# robocon_line_following_sensor_compact.net
KiCad netlist of a schematic drawn in EAGLE
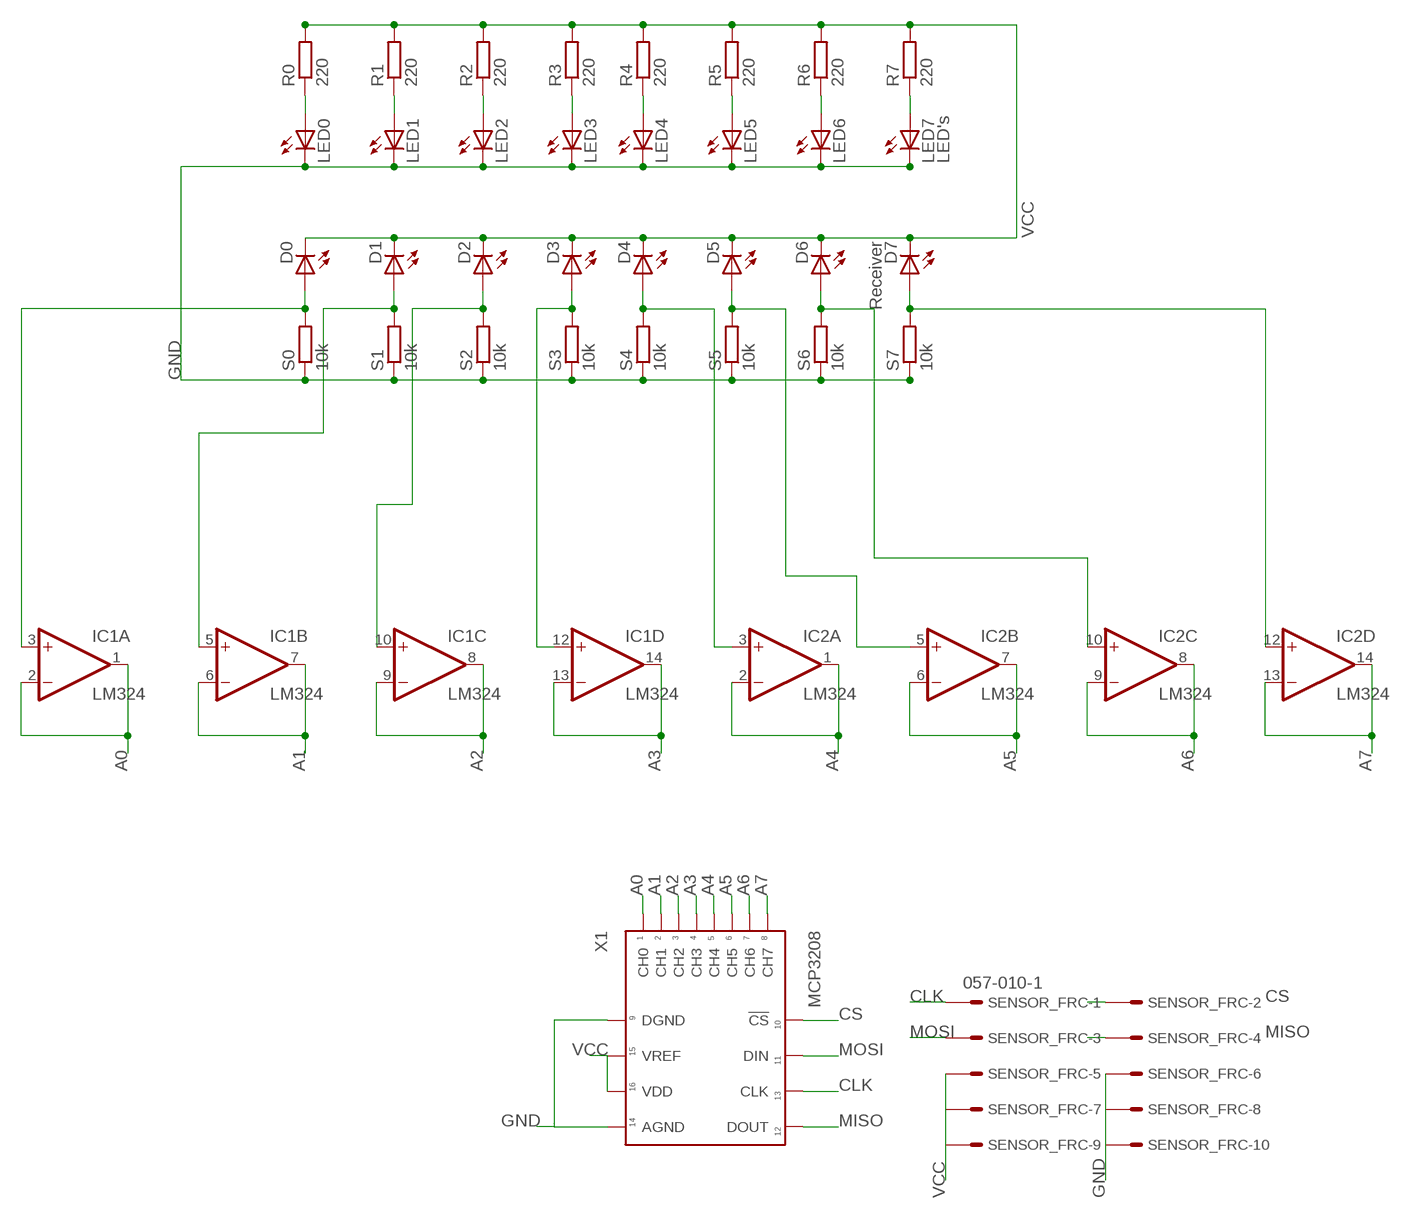
[diagram p0: schematic, sheet 1]

(export (version "E")
  (design (tool "Eeschema 10.0.6"))
  (components
    (comp (ref "D0")
      (value "LED5MM")
      (footprint "eagle-import:LED5MM")
      (libsource (lib "eagle-import") (part "LED5MM"))
    )
    (comp (ref "D1")
      (value "LED5MM")
      (footprint "eagle-import:LED5MM")
      (libsource (lib "eagle-import") (part "LED5MM"))
    )
    (comp (ref "D2")
      (value "LED5MM")
      (footprint "eagle-import:LED5MM")
      (libsource (lib "eagle-import") (part "LED5MM"))
    )
    (comp (ref "D3")
      (value "LED5MM")
      (footprint "eagle-import:LED5MM")
      (libsource (lib "eagle-import") (part "LED5MM"))
    )
    (comp (ref "D4")
      (value "LED5MM")
      (footprint "eagle-import:LED5MM")
      (libsource (lib "eagle-import") (part "LED5MM"))
    )
    (comp (ref "D5")
      (value "LED5MM")
      (footprint "eagle-import:LED5MM")
      (libsource (lib "eagle-import") (part "LED5MM"))
    )
    (comp (ref "D6")
      (value "LED5MM")
      (footprint "eagle-import:LED5MM")
      (libsource (lib "eagle-import") (part "LED5MM"))
    )
    (comp (ref "D7")
      (value "Receiver")
      (footprint "eagle-import:LED5MM")
      (libsource (lib "eagle-import") (part "LED5MM"))
    )
    (comp (ref "IC1")
      (value "LM324")
      (footprint "eagle-import:DIL14")
      (libsource (lib "eagle-import") (part "LM324N"))
    )
    (comp (ref "IC2")
      (value "LM324")
      (footprint "eagle-import:DIL14")
      (libsource (lib "eagle-import") (part "LM324N"))
    )
    (comp (ref "LED0")
      (value "LED5MM")
      (footprint "eagle-import:LED5MM")
      (libsource (lib "eagle-import") (part "LED5MM"))
    )
    (comp (ref "LED1")
      (value "LED5MM")
      (footprint "eagle-import:LED5MM")
      (libsource (lib "eagle-import") (part "LED5MM"))
    )
    (comp (ref "LED2")
      (value "LED5MM")
      (footprint "eagle-import:LED5MM")
      (libsource (lib "eagle-import") (part "LED5MM"))
    )
    (comp (ref "LED3")
      (value "LED5MM")
      (footprint "eagle-import:LED5MM")
      (libsource (lib "eagle-import") (part "LED5MM"))
    )
    (comp (ref "LED4")
      (value "LED5MM")
      (footprint "eagle-import:LED5MM")
      (libsource (lib "eagle-import") (part "LED5MM"))
    )
    (comp (ref "LED5")
      (value "LED5MM")
      (footprint "eagle-import:LED5MM")
      (libsource (lib "eagle-import") (part "LED5MM"))
    )
    (comp (ref "LED6")
      (value "LED5MM")
      (footprint "eagle-import:LED5MM")
      (libsource (lib "eagle-import") (part "LED5MM"))
    )
    (comp (ref "LED7")
      (value "LED's")
      (footprint "eagle-import:LED5MM")
      (libsource (lib "eagle-import") (part "LED5MM"))
    )
    (comp (ref "R0")
      (value "220")
      (footprint "eagle-import:0207_10")
      (libsource (lib "eagle-import") (part "R-EU_0207/10"))
    )
    (comp (ref "R1")
      (value "220")
      (footprint "eagle-import:0207_10")
      (libsource (lib "eagle-import") (part "R-EU_0207/10"))
    )
    (comp (ref "R2")
      (value "220")
      (footprint "eagle-import:0207_10")
      (libsource (lib "eagle-import") (part "R-EU_0207/10"))
    )
    (comp (ref "R3")
      (value "220")
      (footprint "eagle-import:0207_10")
      (libsource (lib "eagle-import") (part "R-EU_0207/10"))
    )
    (comp (ref "R4")
      (value "220")
      (footprint "eagle-import:0207_10")
      (libsource (lib "eagle-import") (part "R-EU_0207/10"))
    )
    (comp (ref "R5")
      (value "220")
      (footprint "eagle-import:0207_10")
      (libsource (lib "eagle-import") (part "R-EU_0207/10"))
    )
    (comp (ref "R6")
      (value "220")
      (footprint "eagle-import:0207_10")
      (libsource (lib "eagle-import") (part "R-EU_0207/10"))
    )
    (comp (ref "R7")
      (value "220")
      (footprint "eagle-import:0207_10")
      (libsource (lib "eagle-import") (part "R-EU_0207/10"))
    )
    (comp (ref "S0")
      (value "10k")
      (footprint "eagle-import:0207_10")
      (libsource (lib "eagle-import") (part "R-EU_0207/10"))
    )
    (comp (ref "S1")
      (value "10k")
      (footprint "eagle-import:0207_10")
      (libsource (lib "eagle-import") (part "R-EU_0207/10"))
    )
    (comp (ref "S2")
      (value "10k")
      (footprint "eagle-import:0207_10")
      (libsource (lib "eagle-import") (part "R-EU_0207/10"))
    )
    (comp (ref "S3")
      (value "10k")
      (footprint "eagle-import:0207_10")
      (libsource (lib "eagle-import") (part "R-EU_0207/10"))
    )
    (comp (ref "S4")
      (value "10k")
      (footprint "eagle-import:0207_10")
      (libsource (lib "eagle-import") (part "R-EU_0207/10"))
    )
    (comp (ref "S5")
      (value "10k")
      (footprint "eagle-import:0207_10")
      (libsource (lib "eagle-import") (part "R-EU_0207/10"))
    )
    (comp (ref "S6")
      (value "10k")
      (footprint "eagle-import:0207_10")
      (libsource (lib "eagle-import") (part "R-EU_0207/10"))
    )
    (comp (ref "S7")
      (value "10k")
      (footprint "eagle-import:0207_10")
      (libsource (lib "eagle-import") (part "R-EU_0207/10"))
    )
    (comp (ref "SENSOR_FRC")
      (value "057-010-1")
      (footprint "eagle-import:057-010-1")
      (libsource (lib "eagle-import") (part "057-010-1"))
    )
    (comp (ref "X1")
      (value "MCP3208")
      (footprint "eagle-import:DIP16")
      (libsource (lib "eagle-import") (part "21298EDIP"))
    )
  )
  (nets
    (net (code "1") (name "/A0") (class "Default")
      (node (ref "IC1") (pin "1") (pinfunction "OUT_1") (pintype "output"))
      (node (ref "IC1") (pin "2") (pinfunction "-IN_2") (pintype "input"))
      (node (ref "X1") (pin "P$1") (pinfunction "CH0_P$1") (pintype "bidirectional"))
    )
    (net (code "2") (name "/A1") (class "Default")
      (node (ref "IC1") (pin "6") (pinfunction "-IN_6") (pintype "input"))
      (node (ref "IC1") (pin "7") (pinfunction "OUT_7") (pintype "output"))
      (node (ref "X1") (pin "P$2") (pinfunction "CH1_P$2") (pintype "bidirectional"))
    )
    (net (code "3") (name "/A2") (class "Default")
      (node (ref "IC1") (pin "8") (pinfunction "OUT_8") (pintype "output"))
      (node (ref "IC1") (pin "9") (pinfunction "-IN_9") (pintype "input"))
      (node (ref "X1") (pin "P$3") (pinfunction "CH2_P$3") (pintype "bidirectional"))
    )
    (net (code "4") (name "/A3") (class "Default")
      (node (ref "IC1") (pin "13") (pinfunction "-IN_13") (pintype "input"))
      (node (ref "IC1") (pin "14") (pinfunction "OUT_14") (pintype "output"))
      (node (ref "X1") (pin "P$4") (pinfunction "CH3_P$4") (pintype "bidirectional"))
    )
    (net (code "5") (name "/A4") (class "Default")
      (node (ref "IC2") (pin "1") (pinfunction "OUT_1") (pintype "output"))
      (node (ref "IC2") (pin "2") (pinfunction "-IN_2") (pintype "input"))
      (node (ref "X1") (pin "P$5") (pinfunction "CH4_P$5") (pintype "bidirectional"))
    )
    (net (code "6") (name "/A5") (class "Default")
      (node (ref "IC2") (pin "6") (pinfunction "-IN_6") (pintype "input"))
      (node (ref "IC2") (pin "7") (pinfunction "OUT_7") (pintype "output"))
      (node (ref "X1") (pin "P$6") (pinfunction "CH5_P$6") (pintype "bidirectional"))
    )
    (net (code "7") (name "/A6") (class "Default")
      (node (ref "IC2") (pin "8") (pinfunction "OUT_8") (pintype "output"))
      (node (ref "IC2") (pin "9") (pinfunction "-IN_9") (pintype "input"))
      (node (ref "X1") (pin "P$7") (pinfunction "CH6_P$7") (pintype "bidirectional"))
    )
    (net (code "8") (name "/A7") (class "Default")
      (node (ref "IC2") (pin "13") (pinfunction "-IN_13") (pintype "input"))
      (node (ref "IC2") (pin "14") (pinfunction "OUT_14") (pintype "output"))
      (node (ref "X1") (pin "P$8") (pinfunction "CH7_P$8") (pintype "bidirectional"))
    )
    (net (code "9") (name "/CLK") (class "Default")
      (node (ref "SENSOR_FRC") (pin "1") (pinfunction "S_1") (pintype "passive"))
      (node (ref "X1") (pin "P$13") (pinfunction "CLK_P$13") (pintype "bidirectional"))
    )
    (net (code "10") (name "/CS") (class "Default")
      (node (ref "SENSOR_FRC") (pin "2") (pinfunction "S_2") (pintype "passive"))
      (node (ref "X1") (pin "P$10") (pinfunction "~{CS}_P$10") (pintype "bidirectional"))
    )
    (net (code "11") (name "/GND") (class "Default")
      (node (ref "LED0") (pin "K") (pinfunction "C_K") (pintype "passive"))
      (node (ref "LED1") (pin "K") (pinfunction "C_K") (pintype "passive"))
      (node (ref "LED2") (pin "K") (pinfunction "C_K") (pintype "passive"))
      (node (ref "LED3") (pin "K") (pinfunction "C_K") (pintype "passive"))
      (node (ref "LED4") (pin "K") (pinfunction "C_K") (pintype "passive"))
      (node (ref "LED5") (pin "K") (pinfunction "C_K") (pintype "passive"))
      (node (ref "LED6") (pin "K") (pinfunction "C_K") (pintype "passive"))
      (node (ref "LED7") (pin "K") (pinfunction "C_K") (pintype "passive"))
      (node (ref "S0") (pin "1") (pinfunction "1_1") (pintype "passive"))
      (node (ref "S1") (pin "1") (pinfunction "1_1") (pintype "passive"))
      (node (ref "S2") (pin "1") (pinfunction "1_1") (pintype "passive"))
      (node (ref "S3") (pin "1") (pinfunction "1_1") (pintype "passive"))
      (node (ref "S4") (pin "1") (pinfunction "1_1") (pintype "passive"))
      (node (ref "S5") (pin "1") (pinfunction "1_1") (pintype "passive"))
      (node (ref "S6") (pin "1") (pinfunction "1_1") (pintype "passive"))
      (node (ref "S7") (pin "1") (pinfunction "1_1") (pintype "passive"))
      (node (ref "SENSOR_FRC") (pin "10") (pinfunction "S_10") (pintype "passive"))
      (node (ref "SENSOR_FRC") (pin "6") (pinfunction "S_6") (pintype "passive"))
      (node (ref "SENSOR_FRC") (pin "8") (pinfunction "S_8") (pintype "passive"))
      (node (ref "X1") (pin "P$14") (pinfunction "AGND_P$14") (pintype "bidirectional"))
      (node (ref "X1") (pin "P$9") (pinfunction "DGND_P$9") (pintype "bidirectional"))
    )
    (net (code "12") (name "/MISO") (class "Default")
      (node (ref "SENSOR_FRC") (pin "4") (pinfunction "S_4") (pintype "passive"))
      (node (ref "X1") (pin "P$12") (pinfunction "DOUT_P$12") (pintype "bidirectional"))
    )
    (net (code "13") (name "/MOSI") (class "Default")
      (node (ref "SENSOR_FRC") (pin "3") (pinfunction "S_3") (pintype "passive"))
      (node (ref "X1") (pin "P$11") (pinfunction "DIN_P$11") (pintype "bidirectional"))
    )
    (net (code "14") (name "/VCC") (class "Default")
      (node (ref "D0") (pin "K") (pinfunction "C_K") (pintype "passive"))
      (node (ref "D1") (pin "K") (pinfunction "C_K") (pintype "passive"))
      (node (ref "D2") (pin "K") (pinfunction "C_K") (pintype "passive"))
      (node (ref "D3") (pin "K") (pinfunction "C_K") (pintype "passive"))
      (node (ref "D4") (pin "K") (pinfunction "C_K") (pintype "passive"))
      (node (ref "D5") (pin "K") (pinfunction "C_K") (pintype "passive"))
      (node (ref "D6") (pin "K") (pinfunction "C_K") (pintype "passive"))
      (node (ref "D7") (pin "K") (pinfunction "C_K") (pintype "passive"))
      (node (ref "R0") (pin "2") (pinfunction "2_2") (pintype "passive"))
      (node (ref "R1") (pin "2") (pinfunction "2_2") (pintype "passive"))
      (node (ref "R2") (pin "2") (pinfunction "2_2") (pintype "passive"))
      (node (ref "R3") (pin "2") (pinfunction "2_2") (pintype "passive"))
      (node (ref "R4") (pin "2") (pinfunction "2_2") (pintype "passive"))
      (node (ref "R5") (pin "2") (pinfunction "2_2") (pintype "passive"))
      (node (ref "R6") (pin "2") (pinfunction "2_2") (pintype "passive"))
      (node (ref "R7") (pin "2") (pinfunction "2_2") (pintype "passive"))
      (node (ref "SENSOR_FRC") (pin "5") (pinfunction "S_5") (pintype "passive"))
      (node (ref "SENSOR_FRC") (pin "7") (pinfunction "S_7") (pintype "passive"))
      (node (ref "SENSOR_FRC") (pin "9") (pinfunction "S_9") (pintype "passive"))
      (node (ref "X1") (pin "P$15") (pinfunction "VREF_P$15") (pintype "bidirectional"))
      (node (ref "X1") (pin "P$16") (pinfunction "VDD_P$16") (pintype "bidirectional"))
    )
    (net (code "15") (name "Net-(IC1A-+IN)") (class "Default")
      (node (ref "D0") (pin "A") (pinfunction "A_A") (pintype "passive"))
      (node (ref "IC1") (pin "3") (pinfunction "+IN_3") (pintype "input"))
      (node (ref "S0") (pin "2") (pinfunction "2_2") (pintype "passive"))
    )
    (net (code "16") (name "Net-(IC1B-+IN)") (class "Default")
      (node (ref "D1") (pin "A") (pinfunction "A_A") (pintype "passive"))
      (node (ref "IC1") (pin "5") (pinfunction "+IN_5") (pintype "input"))
      (node (ref "S1") (pin "2") (pinfunction "2_2") (pintype "passive"))
    )
    (net (code "17") (name "Net-(IC1C-+IN)") (class "Default")
      (node (ref "D2") (pin "A") (pinfunction "A_A") (pintype "passive"))
      (node (ref "IC1") (pin "10") (pinfunction "+IN_10") (pintype "input"))
      (node (ref "S2") (pin "2") (pinfunction "2_2") (pintype "passive"))
    )
    (net (code "18") (name "Net-(IC1D-+IN)") (class "Default")
      (node (ref "D3") (pin "A") (pinfunction "A_A") (pintype "passive"))
      (node (ref "IC1") (pin "12") (pinfunction "+IN_12") (pintype "input"))
      (node (ref "S3") (pin "2") (pinfunction "2_2") (pintype "passive"))
    )
    (net (code "19") (name "Net-(IC2A-+IN)") (class "Default")
      (node (ref "D4") (pin "A") (pinfunction "A_A") (pintype "passive"))
      (node (ref "IC2") (pin "3") (pinfunction "+IN_3") (pintype "input"))
      (node (ref "S4") (pin "2") (pinfunction "2_2") (pintype "passive"))
    )
    (net (code "20") (name "Net-(IC2B-+IN)") (class "Default")
      (node (ref "D5") (pin "A") (pinfunction "A_A") (pintype "passive"))
      (node (ref "IC2") (pin "5") (pinfunction "+IN_5") (pintype "input"))
      (node (ref "S5") (pin "2") (pinfunction "2_2") (pintype "passive"))
    )
    (net (code "21") (name "Net-(IC2C-+IN)") (class "Default")
      (node (ref "D6") (pin "A") (pinfunction "A_A") (pintype "passive"))
      (node (ref "IC2") (pin "10") (pinfunction "+IN_10") (pintype "input"))
      (node (ref "S6") (pin "2") (pinfunction "2_2") (pintype "passive"))
    )
    (net (code "22") (name "Net-(IC2D-+IN)") (class "Default")
      (node (ref "D7") (pin "A") (pinfunction "A_A") (pintype "passive"))
      (node (ref "IC2") (pin "12") (pinfunction "+IN_12") (pintype "input"))
      (node (ref "S7") (pin "2") (pinfunction "2_2") (pintype "passive"))
    )
    (net (code "23") (name "Net-(LED0-PadA)") (class "Default")
      (node (ref "LED0") (pin "A") (pinfunction "A_A") (pintype "passive"))
      (node (ref "R0") (pin "1") (pinfunction "1_1") (pintype "passive"))
    )
    (net (code "24") (name "Net-(LED1-PadA)") (class "Default")
      (node (ref "LED1") (pin "A") (pinfunction "A_A") (pintype "passive"))
      (node (ref "R1") (pin "1") (pinfunction "1_1") (pintype "passive"))
    )
    (net (code "25") (name "Net-(LED2-PadA)") (class "Default")
      (node (ref "LED2") (pin "A") (pinfunction "A_A") (pintype "passive"))
      (node (ref "R2") (pin "1") (pinfunction "1_1") (pintype "passive"))
    )
    (net (code "26") (name "Net-(LED3-PadA)") (class "Default")
      (node (ref "LED3") (pin "A") (pinfunction "A_A") (pintype "passive"))
      (node (ref "R3") (pin "1") (pinfunction "1_1") (pintype "passive"))
    )
    (net (code "27") (name "Net-(LED4-PadA)") (class "Default")
      (node (ref "LED4") (pin "A") (pinfunction "A_A") (pintype "passive"))
      (node (ref "R4") (pin "1") (pinfunction "1_1") (pintype "passive"))
    )
    (net (code "28") (name "Net-(LED5-PadA)") (class "Default")
      (node (ref "LED5") (pin "A") (pinfunction "A_A") (pintype "passive"))
      (node (ref "R5") (pin "1") (pinfunction "1_1") (pintype "passive"))
    )
    (net (code "29") (name "Net-(LED6-PadA)") (class "Default")
      (node (ref "LED6") (pin "A") (pinfunction "A_A") (pintype "passive"))
      (node (ref "R6") (pin "1") (pinfunction "1_1") (pintype "passive"))
    )
    (net (code "30") (name "Net-(LED7-PadA)") (class "Default")
      (node (ref "LED7") (pin "A") (pinfunction "A_A") (pintype "passive"))
      (node (ref "R7") (pin "1") (pinfunction "1_1") (pintype "passive"))
    )
  )
)
